# USB_Serial_Interface.net
KiCad netlist of a schematic drawn in Altium Designer
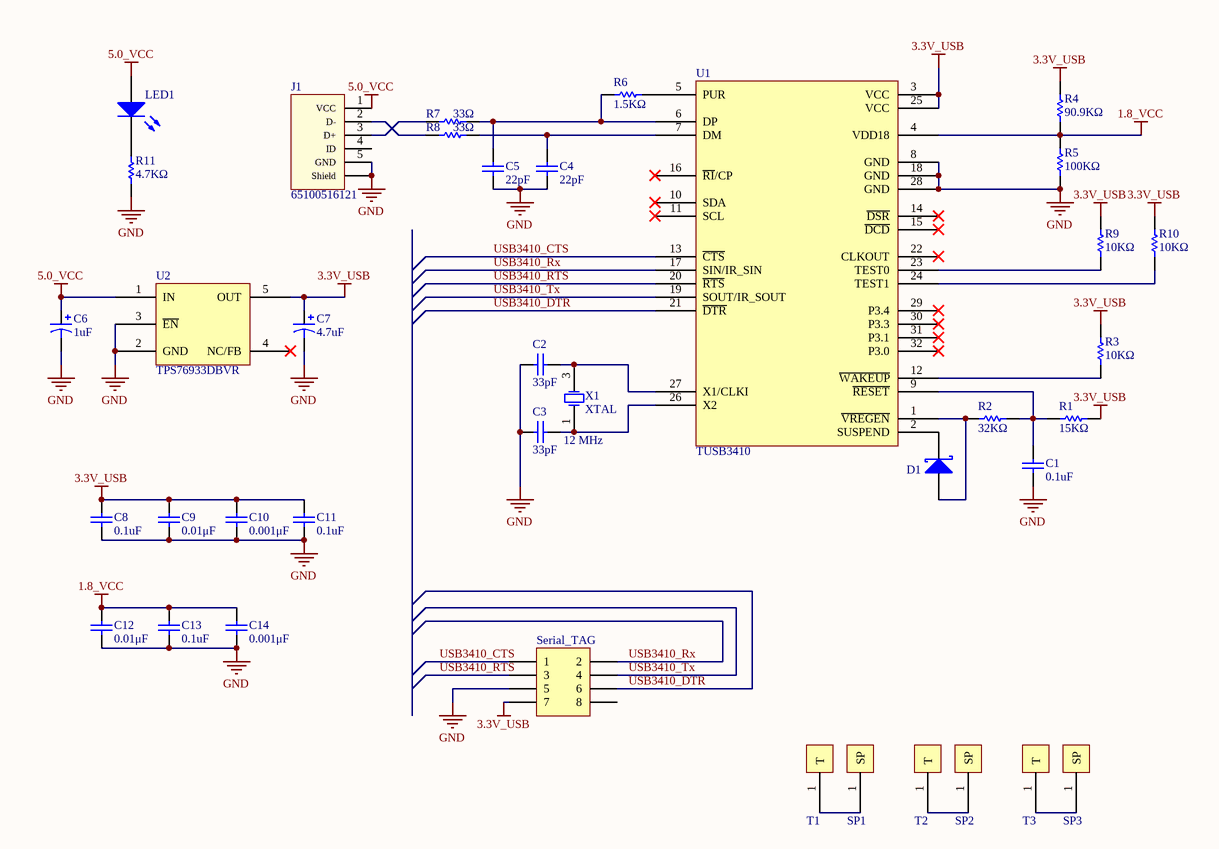
[diagram p0: USB_Serial_Interface.SchDoc]

(export (version "E")
  (design (tool "Eeschema 10.0.6"))
  (components
    (comp (ref "C1")
      (value "0.1uF")
      (footprint "0603 - CAP")
      (description "CAP CERAMIC 0.1UF, 25V, X7R, 0603")
      (fields
        (field (name "MANUFACTURER PART NUMBER") "CGJ3E2X7R1E104K080AA")
        (field (name "MANUFACTURER") "TDK Corporation")
      )
      (libsource (lib "*") (part "Cap"))
    )
    (comp (ref "C2")
      (value "33pF")
      (footprint "0603 - CAP")
      (description "CAP CER 33PF 100V C0G/NP0 0603")
      (fields
        (field (name "MANUFACTURER") "AVX Corporation")
        (field (name "MANUFACTURER PART NUMBER") "06031A330FAT2A")
      )
      (libsource (lib "Miscellaneous Devices") (part "Cap"))
    )
    (comp (ref "C3")
      (value "33pF")
      (footprint "0603 - CAP")
      (description "CAP CER 33PF 100V C0G/NP0 0603")
      (fields
        (field (name "MANUFACTURER") "AVX Corporation")
        (field (name "MANUFACTURER PART NUMBER") "06031A330FAT2A")
      )
      (libsource (lib "Miscellaneous Devices") (part "Cap"))
    )
    (comp (ref "C4")
      (value "22pF")
      (footprint "0603 - CAP")
      (description "CAP CER 22PF 25V C0G/NP0 0603")
      (fields
        (field (name "MANUFACTURER PART NUMBER") "C0603C220K3GACTU")
        (field (name "MANUFACTURER") "Kemet")
      )
      (libsource (lib "Miscellaneous Devices") (part "Cap"))
    )
    (comp (ref "C5")
      (value "22pF")
      (footprint "0603 - CAP")
      (description "CAP CER 22PF 25V C0G/NP0 0603")
      (fields
        (field (name "MANUFACTURER PART NUMBER") "C0603C220K3GACTU")
        (field (name "MANUFACTURER") "Kemet")
      )
      (libsource (lib "Miscellaneous Devices") (part "Cap"))
    )
    (comp (ref "C6")
      (value "1uF")
      (footprint "0805-tan")
      (description "CAP TANT 1UF 10V 10% 0805")
      (fields
        (field (name "MANUFACTURER") "AVX Corporation")
        (field (name "MANUFACTURER PART NUMBER") "TAJR105K010RNJ")
      )
      (libsource (lib "Miscellaneous Devices") (part "Cap Pol1"))
    )
    (comp (ref "C7")
      (value "4.7uF")
      (footprint "0805-tan")
      (description "CAP TANT 4.7UF 10V 10% 0805")
      (fields
        (field (name "MANUFACTURER PART NUMBER") "TAJR475K010RNJ")
        (field (name "MANUFACTURER") "AVX Corporation")
      )
      (libsource (lib "Miscellaneous Devices") (part "Cap Pol1"))
    )
    (comp (ref "C8")
      (value "0.1uF")
      (footprint "0603 - CAP")
      (description "CAP CERAMIC 0.1UF, 25V, X7R, 0603")
      (fields
        (field (name "MANUFACTURER PART NUMBER") "CGJ3E2X7R1E104K080AA")
        (field (name "MANUFACTURER") "TDK Corporation")
      )
      (libsource (lib "*") (part "Cap"))
    )
    (comp (ref "C9")
      (value "0.01μF")
      (footprint "0603 - CAP")
      (description "CAP CER 10000PF 16V X7R 0603")
      (fields
        (field (name "MANUFACTURER") "Kemet")
        (field (name "MANUFACTURER PART NUMBER") "C0603C103K4RACTU")
      )
      (libsource (lib "Miscellaneous Devices") (part "Cap"))
    )
    (comp (ref "C10")
      (value "0.001μF")
      (footprint "0603 - CAP")
      (description "CAP CER 1000PF 16V X7R 0603")
      (fields (field (name "MANUFACTURER PART NUMBER") "0603YC102KAT2A"))
      (libsource (lib "Miscellaneous Devices") (part "Cap"))
    )
    (comp (ref "C11")
      (value "0.1uF")
      (footprint "0603 - CAP")
      (description "CAP CERAMIC 0.1UF, 25V, X7R, 0603")
      (fields
        (field (name "MANUFACTURER PART NUMBER") "CGJ3E2X7R1E104K080AA")
        (field (name "MANUFACTURER") "TDK Corporation")
      )
      (libsource (lib "*") (part "Cap"))
    )
    (comp (ref "C12")
      (value "0.01μF")
      (footprint "0603 - CAP")
      (description "CAP CER 10000PF 16V X7R 0603")
      (fields
        (field (name "MANUFACTURER") "Kemet")
        (field (name "MANUFACTURER PART NUMBER") "C0603C103K4RACTU")
      )
      (libsource (lib "Miscellaneous Devices") (part "Cap"))
    )
    (comp (ref "C13")
      (value "0.1uF")
      (footprint "0603 - CAP")
      (description "CAP CERAMIC 0.1UF, 25V, X7R, 0603")
      (fields
        (field (name "MANUFACTURER PART NUMBER") "CGJ3E2X7R1E104K080AA")
        (field (name "MANUFACTURER") "TDK Corporation")
      )
      (libsource (lib "*") (part "Cap"))
    )
    (comp (ref "C14")
      (value "0.001μF")
      (footprint "0603 - CAP")
      (description "CAP CER 1000PF 16V X7R 0603")
      (fields (field (name "MANUFACTURER PART NUMBER") "0603YC102KAT2A"))
      (libsource (lib "Miscellaneous Devices") (part "Cap"))
    )
    (comp (ref "D1")
      (value "NSR0320MW2T1G")
      (footprint "SOD-323")
      (description "DIODE SCHOTTKY 1A 20V SOD-323")
      (fields (field (name "MANUFACTURER") "ON Semiconductor"))
      (libsource (lib "IR Discrete Rectifier - Schottky") (part "10MQ060N"))
    )
    (comp (ref "J1")
      (value "65100516121")
      (footprint "65100516121")
      (description "Mini USB 2.0 Type B SMT Horizontal 5 Contacts WR-COM")
      (libsource (lib "ALTIUM-WR-COM-rev18a") (part "65100516121"))
    )
    (comp (ref "LED1")
      (value "LED1")
      (footprint "0805-LEDG")
      (description "WL-SMCW SMD mono-color chip LED waterclear 0805 Green")
      (fields
        (field (name "MANUFACTURER") "WURTH ELEKTRONIK")
        (field (name "MANUFACTURER PART NUMBER") "150080GS75000")
      )
      (libsource (lib "Miscellaneous Devices") (part "LED2"))
    )
    (comp (ref "R1")
      (value "15KΩ")
      (footprint "0805-RES")
      (description "RES SMD 15K OHM 0.1% 1/4W 0805")
      (fields
        (field (name "MANUFACTURER") "Panasonic Electronic Components")
        (field (name "MANUFACTURER PART NUMBER") "ERJ-PB6B1502V")
      )
      (libsource (lib "Miscellaneous Devices") (part "Res Semi"))
    )
    (comp (ref "R2")
      (value "32KΩ")
      (footprint "0402")
      (description "RES 32K OHM 0.1% 1/10W 0402")
      (fields
        (field (name "MANUFACTURER PART NUMBER") "TNPW040232K0BEED")
        (field (name "MANUFACTURER") "Vishay Dale")
      )
      (libsource (lib "Miscellaneous Devices") (part "Res Semi"))
    )
    (comp (ref "R3")
      (value "10KΩ")
      (footprint "0805-RES")
      (description "10 kOhms ±5% 0.125W, 1/8W Chip Resistor 0805")
      (fields
        (field (name "MANUFACTURER PART NUMBER") "RC0805JR-0710KL")
        (field (name "MANUFACTURER") "Yageo")
      )
      (libsource (lib "Miscellaneous Devices") (part "Res Semi"))
    )
    (comp (ref "R4")
      (value "90.9KΩ")
      (footprint "0805-RES")
      (description "RES SMD 90.9K OHM 0.1% 1/8W 0805")
      (fields
        (field (name "MANUFACTURER") "Panasonic Electronic Components")
        (field (name "MANUFACTURER PART NUMBER") "ERA-6AEB9092V")
      )
      (libsource (lib "Miscellaneous Devices") (part "Res Semi"))
    )
    (comp (ref "R5")
      (value "100KΩ")
      (footprint "0805-RES")
      (description "RES SMD 100K OHM 0.1% 1/8W 0805")
      (fields
        (field (name "MANUFACTURER") "Panasonic Electronic Components")
        (field (name "MANUFACTURER PART NUMBER") "ERA-6AEB104V")
      )
      (libsource (lib "LibreriaEstandar") (part "Res1"))
    )
    (comp (ref "R6")
      (value "1.5KΩ")
      (footprint "0805-RES")
      (description "RES SMD 1.5K OHM 5% 0.4W 0805")
      (fields
        (field (name "MANUFACTURER") "Rohm Semiconductor")
        (field (name "MANUFACTURER PART NUMBER") "ESR10EZPJ152")
      )
      (libsource (lib "Miscellaneous Devices") (part "Res Semi"))
    )
    (comp (ref "R7")
      (value "33Ω")
      (footprint "0805-RES")
      (description "RES SMD 33 OHM 1% 1/8W 0805")
      (fields
        (field (name "MANUFACTURER") "Yageo")
        (field (name "MANUFACTURER PART NUMBER") "RC0805FR-0733RL")
      )
      (libsource (lib "Miscellaneous Devices") (part "Res Semi"))
    )
    (comp (ref "R8")
      (value "33Ω")
      (footprint "0805-RES")
      (description "RES SMD 33 OHM 1% 1/8W 0805")
      (fields
        (field (name "MANUFACTURER") "Yageo")
        (field (name "MANUFACTURER PART NUMBER") "RC0805FR-0733RL")
      )
      (libsource (lib "Miscellaneous Devices") (part "Res Semi"))
    )
    (comp (ref "R9")
      (value "10KΩ")
      (footprint "0805-RES")
      (description "10 kOhms ±5% 0.125W, 1/8W Chip Resistor 0805")
      (fields
        (field (name "MANUFACTURER PART NUMBER") "RC0805JR-0710KL")
        (field (name "MANUFACTURER") "Yageo")
      )
      (libsource (lib "Miscellaneous Devices") (part "Res Semi"))
    )
    (comp (ref "R10")
      (value "10KΩ")
      (footprint "0805-RES")
      (description "10 kOhms ±5% 0.125W, 1/8W Chip Resistor 0805")
      (fields
        (field (name "MANUFACTURER PART NUMBER") "RC0805JR-0710KL")
        (field (name "MANUFACTURER") "Yageo")
      )
      (libsource (lib "Miscellaneous Devices") (part "Res Semi"))
    )
    (comp (ref "R11")
      (value "4.7KΩ")
      (footprint "0805-RES")
      (description "RES SMD 4.7K OHM 5% 1/8W 0805")
      (fields
        (field (name "MANUFACTURER") "Yageo")
        (field (name "MANUFACTURER PART NUMBER") "RC0805JR-074K7L")
      )
      (libsource (lib "Miscellaneous Devices") (part "Res1"))
    )
    (comp (ref "Serial_TAG")
      (value "Header 4X2")
      (footprint "690367290876")
      (description "Female SMT Straight Connector with Latch and with Polarization WR-MM 8-Pin")
      (fields (field (name "MANUFACTURER PART NUMBER") "690 367 290 876"))
      (libsource (lib "Miscellaneous Connectors") (part "Header 4X2"))
    )
    (comp (ref "SP1")
      (value "~")
      (footprint "SPACER")
      (description "No Aplica")
      (libsource (lib "") (part "PRUEBA_1"))
    )
    (comp (ref "SP2")
      (value "~")
      (footprint "SPACER")
      (description "No Aplica")
      (libsource (lib "") (part "PRUEBA_1"))
    )
    (comp (ref "SP3")
      (value "~")
      (footprint "SPACER")
      (description "No Aplica")
      (libsource (lib "") (part "PRUEBA_1"))
    )
    (comp (ref "T1")
      (value "~")
      (footprint "Tornillo")
      (description "No Aplica")
      (libsource (lib "LibreriaEstandar2") (part "PRUEBA"))
    )
    (comp (ref "T2")
      (value "~")
      (footprint "Tornillo")
      (description "No Aplica")
      (libsource (lib "LibreriaEstandar2") (part "PRUEBA"))
    )
    (comp (ref "T3")
      (value "~")
      (footprint "Tornillo")
      (description "No Aplica")
      (libsource (lib "LibreriaEstandar2") (part "PRUEBA"))
    )
    (comp (ref "U1")
      (value "TUSB3410")
      (footprint "Quad32")
      (fields
        (field (name "MANUFACTURER") "Texas Instruments")
        (field (name "MANUFACTURER PART NUMBER") "TUSB3410IVF")
      )
      (libsource (lib "TexasInstruments_Custom") (part "TUSB3410"))
    )
    (comp (ref "U2")
      (value "TPS76933DBVR")
      (footprint "DBV005")
      (description "Linear Voltage Regulator IC Positive Fixed 1 Output 3.3V 100mA SOT-23-5")
      (fields
        (field (name "MANUFACTURER") "Texas Instruments")
        (field (name "MANUFACTURER PART NUMBER") "TPS76933DBVT")
      )
      (libsource (lib "TexasInstruments_Custom") (part "TPS76933"))
    )
    (comp (ref "X1")
      (value "XTAL")
      (footprint "XTAL 4-SMD")
      (description "CRYSTAL 12.0000MHZ 18PF SMD")
      (fields
        (field (name "ALTIUM_VALUE") "12 MHz")
        (field (name "MANUFACTURER") "AVX Corp/Kyocera Corp")
        (field (name "MANUFACTURER PART NUMBER") "CX3225GB12000P0HPQCC")
      )
      (libsource (lib "Miscellaneous Devices") (part "XTAL"))
    )
  )
  (nets
    (net (code "1") (name "/USB3410_CTS") (class "Default")
      (node (ref "Serial_TAG") (pin "1") (pinfunction "1_1") (pintype "passive"))
      (node (ref "U1") (pin "13") (pinfunction "~{CTS}_13") (pintype "passive"))
    )
    (net (code "2") (name "/USB3410_DTR") (class "Default")
      (node (ref "Serial_TAG") (pin "6") (pinfunction "6_6") (pintype "passive"))
      (node (ref "U1") (pin "21") (pinfunction "~{DTR}_21") (pintype "passive"))
    )
    (net (code "3") (name "/USB3410_RTS") (class "Default")
      (node (ref "Serial_TAG") (pin "3") (pinfunction "3_3") (pintype "passive"))
      (node (ref "U1") (pin "20") (pinfunction "~{RTS}_20") (pintype "passive"))
    )
    (net (code "4") (name "/USB3410_Rx") (class "Default")
      (node (ref "Serial_TAG") (pin "2") (pinfunction "2_2") (pintype "passive"))
      (node (ref "U1") (pin "17") (pinfunction "SIN/IR_SIN_17") (pintype "passive"))
    )
    (net (code "5") (name "/USB3410_Tx") (class "Default")
      (node (ref "Serial_TAG") (pin "4") (pinfunction "4_4") (pintype "passive"))
      (node (ref "U1") (pin "19") (pinfunction "SOUT/IR_SOUT_19") (pintype "passive"))
    )
    (net (code "6") (name "1.8_VCC") (class "Default")
      (node (ref "C12") (pin "2") (pinfunction "2_2") (pintype "passive"))
      (node (ref "C13") (pin "1") (pinfunction "1_1") (pintype "passive"))
      (node (ref "C14") (pin "2") (pinfunction "2_2") (pintype "passive"))
      (node (ref "R4") (pin "2") (pinfunction "2_2") (pintype "passive"))
      (node (ref "R5") (pin "2") (pinfunction "2_2") (pintype "passive"))
      (node (ref "U1") (pin "4") (pinfunction "VDD18_4") (pintype "passive"))
    )
    (net (code "7") (name "3.3V_USB") (class "Default")
      (node (ref "C10") (pin "2") (pinfunction "2_2") (pintype "passive"))
      (node (ref "C11") (pin "1") (pinfunction "1_1") (pintype "passive"))
      (node (ref "C7") (pin "1") (pinfunction "1_1") (pintype "passive"))
      (node (ref "C8") (pin "1") (pinfunction "1_1") (pintype "passive"))
      (node (ref "C9") (pin "2") (pinfunction "2_2") (pintype "passive"))
      (node (ref "R1") (pin "1") (pinfunction "1_1") (pintype "passive"))
      (node (ref "R10") (pin "1") (pinfunction "1_1") (pintype "passive"))
      (node (ref "R3") (pin "1") (pinfunction "1_1") (pintype "passive"))
      (node (ref "R4") (pin "1") (pinfunction "1_1") (pintype "passive"))
      (node (ref "R9") (pin "1") (pinfunction "1_1") (pintype "passive"))
      (node (ref "Serial_TAG") (pin "7") (pinfunction "7_7") (pintype "passive"))
      (node (ref "U1") (pin "25") (pinfunction "VCC_25") (pintype "passive"))
      (node (ref "U1") (pin "3") (pinfunction "VCC_3") (pintype "passive"))
      (node (ref "U2") (pin "5") (pinfunction "OUT_5") (pintype "passive"))
    )
    (net (code "8") (name "5.0_VCC") (class "Default")
      (node (ref "C6") (pin "1") (pinfunction "1_1") (pintype "passive"))
      (node (ref "J1") (pin "1") (pinfunction "VCC_1") (pintype "passive"))
      (node (ref "LED1") (pin "1") (pinfunction "A_1") (pintype "passive"))
      (node (ref "U2") (pin "1") (pinfunction "IN_1") (pintype "passive"))
    )
    (net (code "9") (name "GND") (class "Default")
      (node (ref "C1") (pin "2") (pinfunction "2_2") (pintype "passive"))
      (node (ref "C10") (pin "1") (pinfunction "1_1") (pintype "passive"))
      (node (ref "C11") (pin "2") (pinfunction "2_2") (pintype "passive"))
      (node (ref "C12") (pin "1") (pinfunction "1_1") (pintype "passive"))
      (node (ref "C13") (pin "2") (pinfunction "2_2") (pintype "passive"))
      (node (ref "C14") (pin "1") (pinfunction "1_1") (pintype "passive"))
      (node (ref "C2") (pin "2") (pinfunction "2_2") (pintype "passive"))
      (node (ref "C3") (pin "2") (pinfunction "2_2") (pintype "passive"))
      (node (ref "C4") (pin "2") (pinfunction "2_2") (pintype "passive"))
      (node (ref "C5") (pin "2") (pinfunction "2_2") (pintype "passive"))
      (node (ref "C6") (pin "2") (pinfunction "2_2") (pintype "passive"))
      (node (ref "C7") (pin "2") (pinfunction "2_2") (pintype "passive"))
      (node (ref "C8") (pin "2") (pinfunction "2_2") (pintype "passive"))
      (node (ref "C9") (pin "1") (pinfunction "1_1") (pintype "passive"))
      (node (ref "J1") (pin "5") (pinfunction "GND_5") (pintype "passive"))
      (node (ref "J1") (pin "Shell") (pinfunction "Shield_Shell") (pintype "passive"))
      (node (ref "R11") (pin "1") (pinfunction "1_1") (pintype "passive"))
      (node (ref "R5") (pin "1") (pinfunction "1_1") (pintype "passive"))
      (node (ref "Serial_TAG") (pin "5") (pinfunction "5_5") (pintype "passive"))
      (node (ref "U1") (pin "18") (pinfunction "GND_18") (pintype "passive"))
      (node (ref "U1") (pin "28") (pinfunction "GND_28") (pintype "passive"))
      (node (ref "U1") (pin "8") (pinfunction "GND_8") (pintype "passive"))
      (node (ref "U2") (pin "2") (pinfunction "GND_2") (pintype "passive"))
      (node (ref "U2") (pin "3") (pinfunction "~{EN}_3") (pintype "passive"))
    )
    (net (code "10") (name "Net-(D1-A)") (class "Default")
      (node (ref "D1") (pin "1") (pinfunction "A_1") (pintype "passive"))
      (node (ref "R2") (pin "2") (pinfunction "2_2") (pintype "passive"))
      (node (ref "U1") (pin "1") (pinfunction "~{VREGEN}_1") (pintype "passive"))
    )
    (net (code "11") (name "Net-(D1-K)") (class "Default")
      (node (ref "D1") (pin "2") (pinfunction "K_2") (pintype "passive"))
      (node (ref "U1") (pin "2") (pinfunction "SUSPEND_2") (pintype "passive"))
    )
    (net (code "12") (name "Net-(J1-D+)") (class "Default")
      (node (ref "J1") (pin "3") (pinfunction "D+_3") (pintype "passive"))
      (node (ref "R7") (pin "1") (pinfunction "1_1") (pintype "passive"))
    )
    (net (code "13") (name "Net-(J1-D-)") (class "Default")
      (node (ref "J1") (pin "2") (pinfunction "D-_2") (pintype "passive"))
      (node (ref "R8") (pin "1") (pinfunction "1_1") (pintype "passive"))
    )
    (net (code "14") (name "Net-(LED1-K)") (class "Default")
      (node (ref "LED1") (pin "2") (pinfunction "K_2") (pintype "passive"))
      (node (ref "R11") (pin "2") (pinfunction "2_2") (pintype "passive"))
    )
    (net (code "15") (name "Net-(SP1-SP)") (class "Default")
      (node (ref "SP1") (pin "1") (pinfunction "SP_1") (pintype "passive"))
      (node (ref "T1") (pin "1") (pinfunction "T_1") (pintype "passive"))
    )
    (net (code "16") (name "Net-(SP2-SP)") (class "Default")
      (node (ref "SP2") (pin "1") (pinfunction "SP_1") (pintype "passive"))
      (node (ref "T2") (pin "1") (pinfunction "T_1") (pintype "passive"))
    )
    (net (code "17") (name "Net-(SP3-SP)") (class "Default")
      (node (ref "SP3") (pin "1") (pinfunction "SP_1") (pintype "passive"))
      (node (ref "T3") (pin "1") (pinfunction "T_1") (pintype "passive"))
    )
    (net (code "18") (name "Net-(U1-DM)") (class "Default")
      (node (ref "C4") (pin "1") (pinfunction "1_1") (pintype "passive"))
      (node (ref "R8") (pin "2") (pinfunction "2_2") (pintype "passive"))
      (node (ref "U1") (pin "7") (pinfunction "DM_7") (pintype "passive"))
    )
    (net (code "19") (name "Net-(U1-DP)") (class "Default")
      (node (ref "C5") (pin "1") (pinfunction "1_1") (pintype "passive"))
      (node (ref "R6") (pin "1") (pinfunction "1_1") (pintype "passive"))
      (node (ref "R7") (pin "2") (pinfunction "2_2") (pintype "passive"))
      (node (ref "U1") (pin "6") (pinfunction "DP_6") (pintype "passive"))
    )
    (net (code "20") (name "Net-(U1-PUR)") (class "Default")
      (node (ref "R6") (pin "2") (pinfunction "2_2") (pintype "passive"))
      (node (ref "U1") (pin "5") (pinfunction "PUR_5") (pintype "passive"))
    )
    (net (code "21") (name "Net-(U1-TEST0)") (class "Default")
      (node (ref "R9") (pin "2") (pinfunction "2_2") (pintype "passive"))
      (node (ref "U1") (pin "23") (pinfunction "TEST0_23") (pintype "passive"))
    )
    (net (code "22") (name "Net-(U1-TEST1)") (class "Default")
      (node (ref "R10") (pin "2") (pinfunction "2_2") (pintype "passive"))
      (node (ref "U1") (pin "24") (pinfunction "TEST1_24") (pintype "passive"))
    )
    (net (code "23") (name "Net-(U1-X1{slash}CLKI)") (class "Default")
      (node (ref "C2") (pin "1") (pinfunction "1_1") (pintype "passive"))
      (node (ref "U1") (pin "27") (pinfunction "X1/CLKI_27") (pintype "passive"))
      (node (ref "X1") (pin "3") (pinfunction "OSC2_3") (pintype "passive"))
    )
    (net (code "24") (name "Net-(U1-X2)") (class "Default")
      (node (ref "C3") (pin "1") (pinfunction "1_1") (pintype "passive"))
      (node (ref "U1") (pin "26") (pinfunction "X2_26") (pintype "passive"))
      (node (ref "X1") (pin "1") (pinfunction "OSC1_1") (pintype "passive"))
    )
    (net (code "25") (name "Net-(U1-~{RESET})") (class "Default")
      (node (ref "C1") (pin "1") (pinfunction "1_1") (pintype "passive"))
      (node (ref "R1") (pin "2") (pinfunction "2_2") (pintype "passive"))
      (node (ref "R2") (pin "1") (pinfunction "1_1") (pintype "passive"))
      (node (ref "U1") (pin "9") (pinfunction "~{RESET}_9") (pintype "passive"))
    )
    (net (code "26") (name "Net-(U1-~{WAKEUP})") (class "Default")
      (node (ref "R3") (pin "2") (pinfunction "2_2") (pintype "passive"))
      (node (ref "U1") (pin "12") (pinfunction "~{WAKEUP}_12") (pintype "passive"))
    )
    (net (code "27") (name "unconnected-(J1-ID-Pad4)") (class "Default")
      (node (ref "J1") (pin "4") (pinfunction "ID_4") (pintype "passive"))
    )
    (net (code "28") (name "unconnected-(Serial_TAG-Pad8)") (class "Default")
      (node (ref "Serial_TAG") (pin "8") (pinfunction "8_8") (pintype "passive"))
    )
    (net (code "29") (name "unconnected-(U1-CLKOUT-Pad22)") (class "Default")
      (node (ref "U1") (pin "22") (pinfunction "CLKOUT_22") (pintype "passive+no_connect"))
    )
    (net (code "30") (name "unconnected-(U1-P3.0-Pad32)") (class "Default")
      (node (ref "U1") (pin "32") (pinfunction "P3.0_32") (pintype "passive+no_connect"))
    )
    (net (code "31") (name "unconnected-(U1-P3.1-Pad31)") (class "Default")
      (node (ref "U1") (pin "31") (pinfunction "P3.1_31") (pintype "passive+no_connect"))
    )
    (net (code "32") (name "unconnected-(U1-P3.3-Pad30)") (class "Default")
      (node (ref "U1") (pin "30") (pinfunction "P3.3_30") (pintype "passive+no_connect"))
    )
    (net (code "33") (name "unconnected-(U1-P3.4-Pad29)") (class "Default")
      (node (ref "U1") (pin "29") (pinfunction "P3.4_29") (pintype "passive+no_connect"))
    )
    (net (code "34") (name "unconnected-(U1-SCL-Pad11)") (class "Default")
      (node (ref "U1") (pin "11") (pinfunction "SCL_11") (pintype "passive+no_connect"))
    )
    (net (code "35") (name "unconnected-(U1-SDA-Pad10)") (class "Default")
      (node (ref "U1") (pin "10") (pinfunction "SDA_10") (pintype "passive+no_connect"))
    )
    (net (code "36") (name "unconnected-(U1-~{DCD}-Pad15)") (class "Default")
      (node (ref "U1") (pin "15") (pinfunction "~{DCD}_15") (pintype "passive+no_connect"))
    )
    (net (code "37") (name "unconnected-(U1-~{DSR}-Pad14)") (class "Default")
      (node (ref "U1") (pin "14") (pinfunction "~{DSR}_14") (pintype "passive+no_connect"))
    )
    (net (code "38") (name "unconnected-(U1-~{RI}{slash}CP-Pad16)") (class "Default")
      (node (ref "U1") (pin "16") (pinfunction "~{RI}/CP_16") (pintype "passive+no_connect"))
    )
    (net (code "39") (name "unconnected-(U2-NC{slash}FB-Pad4)") (class "Default")
      (node (ref "U2") (pin "4") (pinfunction "NC/FB_4") (pintype "passive+no_connect"))
    )
  )
)
